# PCF8563.net
KiCad netlist of a schematic drawn in Altium Designer
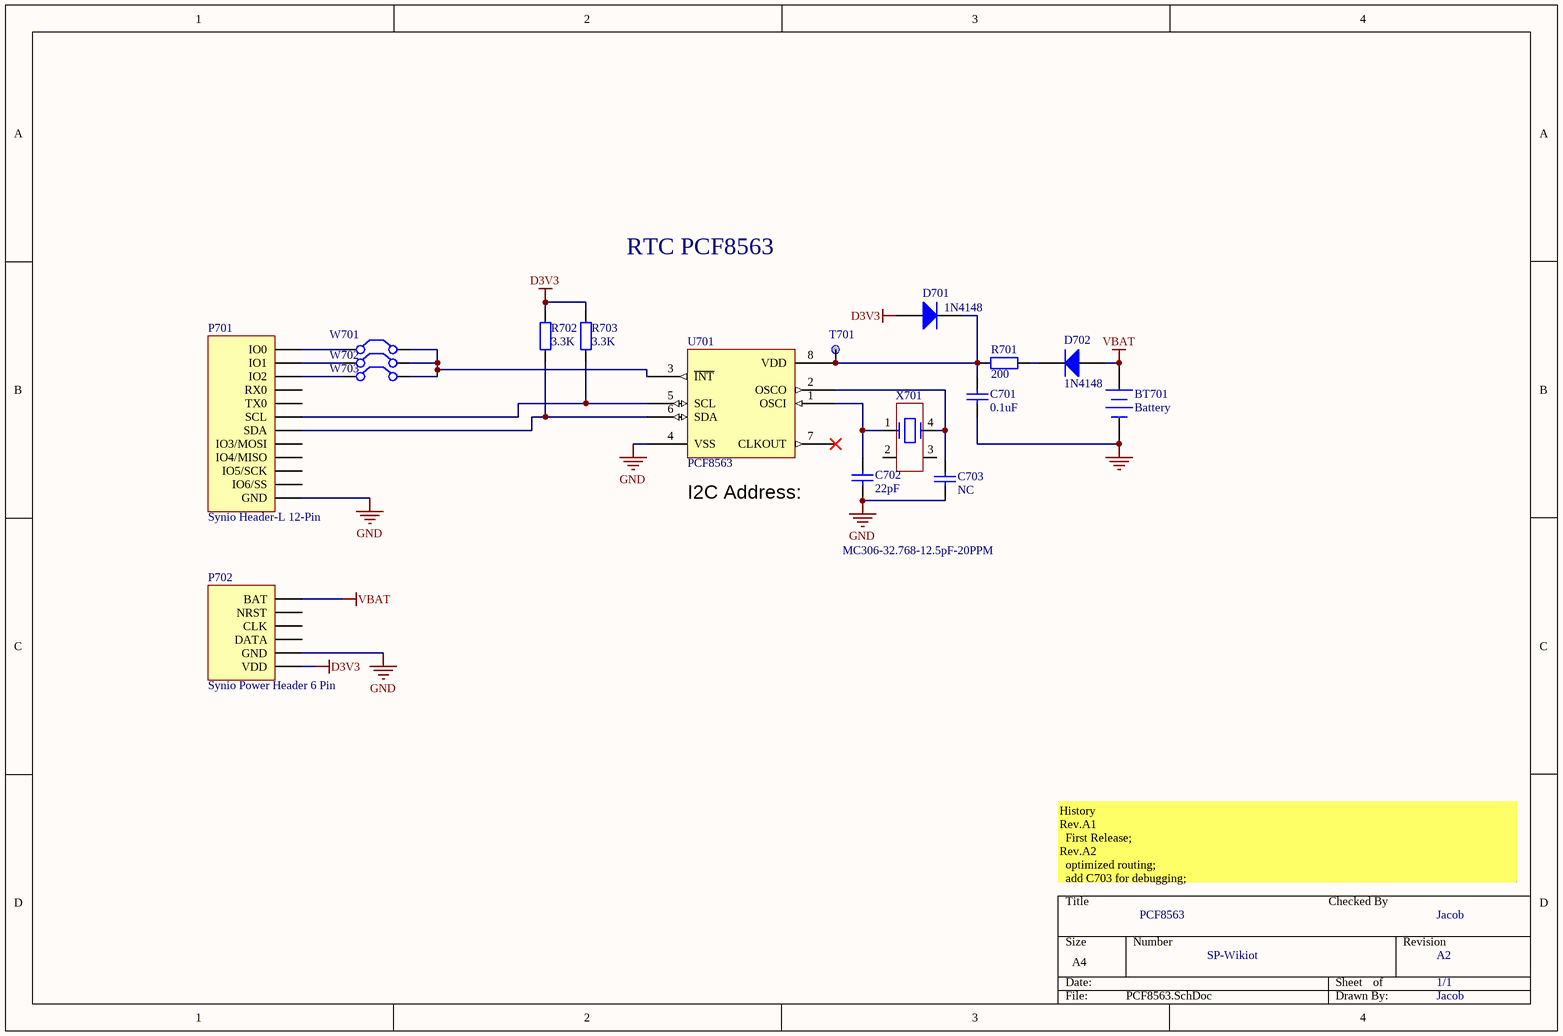
[diagram p0: PCF8563.SchDoc]

(export (version "E")
  (design (tool "Eeschema 10.0.6"))
  (components
    (comp (ref "BT701")
      (value "Battery")
      (footprint "BAT CR1220")
      (description "Multicell Battery")
      (fields (field (name "PUBLISHER") "Altium Limited"))
      (libsource (lib "Miscellaneous Devices") (part "Battery"))
    )
    (comp (ref "C701")
      (value "0.1uF")
      (footprint "0603M")
      (description "Capacitor")
      (libsource (lib "Studio") (part "Cap"))
    )
    (comp (ref "C702")
      (value "22pF")
      (footprint "0603M")
      (description "Capacitor")
      (libsource (lib "Studio") (part "Cap"))
    )
    (comp (ref "C703")
      (value "NC")
      (footprint "0603M")
      (description "Capacitor")
      (libsource (lib "Studio") (part "Cap"))
    )
    (comp (ref "D701")
      (value "1N4148")
      (footprint "1206")
      (description "1 Amp General Purpose Rectifier")
      (fields (field (name "PUBLISHER") "Altium Limited"))
      (libsource (lib "Misc") (part "Diode 1N4007"))
    )
    (comp (ref "D702")
      (value "1N4148")
      (footprint "1206")
      (description "1 Amp General Purpose Rectifier")
      (fields (field (name "PUBLISHER") "Altium Limited"))
      (libsource (lib "Misc") (part "Diode 1N4007"))
    )
    (comp (ref "P701")
      (value "Synio Header-L 12-Pin")
      (footprint "HDR1X12")
      (description "Synio Header-L, 12-Pin")
      (fields (field (name "PUBLISHER") "Altium Limited"))
      (libsource (lib "Connector") (part "Synio Header-L 12-Pin"))
    )
    (comp (ref "P702")
      (value "Synio Power Header 6 Pin")
      (footprint "HDR1X6/2.54MM")
      (libsource (lib "Connector") (part "Synio Power Header 6 Pin"))
    )
    (comp (ref "R701")
      (value "200")
      (footprint "R0603")
      (description "Resistor")
      (fields (field (name "PUBLISHER") "Altium Limited"))
      (libsource (lib "") (part "Res2_1"))
    )
    (comp (ref "R702")
      (value "3.3K")
      (footprint "R0603")
      (description "Resistor")
      (fields (field (name "PUBLISHER") "Altium Limited"))
      (libsource (lib "Miscellaneous Devices") (part "Res2"))
    )
    (comp (ref "R703")
      (value "3.3K")
      (footprint "R0603")
      (description "Resistor")
      (fields (field (name "PUBLISHER") "Altium Limited"))
      (libsource (lib "Miscellaneous Devices") (part "Res2"))
    )
    (comp (ref "T701")
      (value "TP")
      (footprint "TP")
      (description "Test Point")
      (libsource (lib "Misc") (part "TP"))
    )
    (comp (ref "U701")
      (value "PCF8563")
      (footprint "SO8W_M")
      (description "Real Time Clock/Calendar")
      (libsource (lib "Logic") (part "PCF8563"))
    )
    (comp (ref "W701")
      (value "Jumper2-1")
      (footprint "HDR1X2/2.00MM")
      (description "Jumper Wire")
      (fields (field (name "PUBLISHER") "Altium Limited"))
      (libsource (lib "Misc") (part "Jumper2-1"))
    )
    (comp (ref "W702")
      (value "Jumper2-1")
      (footprint "HDR1X2/2.00MM")
      (description "Jumper Wire")
      (fields (field (name "PUBLISHER") "Altium Limited"))
      (libsource (lib "Misc") (part "Jumper2-1"))
    )
    (comp (ref "W703")
      (value "Jumper2-1")
      (footprint "HDR1X2/2.00MM")
      (description "Jumper Wire")
      (fields (field (name "PUBLISHER") "Altium Limited"))
      (libsource (lib "Misc") (part "Jumper2-1"))
    )
    (comp (ref "X701")
      (value "MC306-32.768-12.5pF-20PPM")
      (footprint "SM8")
      (libsource (lib "Misc") (part "MC306"))
    )
  )
  (nets
    (net (code "1") (name "D3V3") (class "Default")
      (node (ref "D701") (pin "1") (pinfunction "A_1") (pintype "passive"))
      (node (ref "P702") (pin "1") (pinfunction "VDD_1") (pintype "passive"))
      (node (ref "R702") (pin "2") (pinfunction "2_2") (pintype "passive"))
      (node (ref "R703") (pin "2") (pinfunction "2_2") (pintype "passive"))
    )
    (net (code "2") (name "GND") (class "Default")
      (node (ref "BT701") (pin "2") (pinfunction "-_2") (pintype "passive"))
      (node (ref "C701") (pin "1") (pinfunction "1_1") (pintype "passive"))
      (node (ref "C702") (pin "1") (pinfunction "1_1") (pintype "passive"))
      (node (ref "C703") (pin "1") (pinfunction "1_1") (pintype "passive"))
      (node (ref "P701") (pin "1") (pinfunction "GND_1") (pintype "passive"))
      (node (ref "P702") (pin "2") (pinfunction "GND_2") (pintype "passive"))
      (node (ref "U701") (pin "4") (pinfunction "VSS_4") (pintype "power_in"))
    )
    (net (code "3") (name "Net-(D701-K)") (class "Default")
      (node (ref "C701") (pin "2") (pinfunction "2_2") (pintype "passive"))
      (node (ref "D701") (pin "2") (pinfunction "K_2") (pintype "passive"))
      (node (ref "R701") (pin "1") (pinfunction "1_1") (pintype "passive"))
      (node (ref "T701") (pin "1") (pinfunction "1_1") (pintype "passive"))
      (node (ref "U701") (pin "8") (pinfunction "VDD_8") (pintype "power_in"))
    )
    (net (code "4") (name "Net-(D702-K)") (class "Default")
      (node (ref "D702") (pin "2") (pinfunction "K_2") (pintype "passive"))
      (node (ref "R701") (pin "2") (pinfunction "2_2") (pintype "passive"))
    )
    (net (code "5") (name "Net-(P701-IO0)") (class "Default")
      (node (ref "P701") (pin "12") (pinfunction "IO0_12") (pintype "passive"))
      (node (ref "W701") (pin "1") (pinfunction "C1_1") (pintype "passive"))
    )
    (net (code "6") (name "Net-(P701-IO1)") (class "Default")
      (node (ref "P701") (pin "11") (pinfunction "IO1_11") (pintype "passive"))
      (node (ref "W702") (pin "1") (pinfunction "C1_1") (pintype "passive"))
    )
    (net (code "7") (name "Net-(P701-IO2)") (class "Default")
      (node (ref "P701") (pin "10") (pinfunction "IO2_10") (pintype "passive"))
      (node (ref "W703") (pin "1") (pinfunction "C1_1") (pintype "passive"))
    )
    (net (code "8") (name "Net-(P701-SCL)") (class "Default")
      (node (ref "P701") (pin "7") (pinfunction "SCL_7") (pintype "passive"))
      (node (ref "R703") (pin "1") (pinfunction "1_1") (pintype "passive"))
      (node (ref "U701") (pin "5") (pinfunction "SCL_5") (pintype "bidirectional"))
    )
    (net (code "9") (name "Net-(P701-SDA)") (class "Default")
      (node (ref "P701") (pin "6") (pinfunction "SDA_6") (pintype "passive"))
      (node (ref "R702") (pin "1") (pinfunction "1_1") (pintype "passive"))
      (node (ref "U701") (pin "6") (pinfunction "SDA_6") (pintype "bidirectional"))
    )
    (net (code "10") (name "Net-(U701-OSCI)") (class "Default")
      (node (ref "C702") (pin "2") (pinfunction "2_2") (pintype "passive"))
      (node (ref "U701") (pin "1") (pinfunction "OSCI_1") (pintype "input"))
      (node (ref "X701") (pin "1") (pinfunction "1_1") (pintype "passive"))
    )
    (net (code "11") (name "Net-(U701-OSCO)") (class "Default")
      (node (ref "C703") (pin "2") (pinfunction "2_2") (pintype "passive"))
      (node (ref "U701") (pin "2") (pinfunction "OSCO_2") (pintype "output"))
      (node (ref "X701") (pin "4") (pinfunction "4_4") (pintype "passive"))
    )
    (net (code "12") (name "Net-(U701-~{INT})") (class "Default")
      (node (ref "U701") (pin "3") (pinfunction "~{INT}_3") (pintype "output"))
      (node (ref "W701") (pin "2") (pinfunction "C2_2") (pintype "passive"))
      (node (ref "W702") (pin "2") (pinfunction "C2_2") (pintype "passive"))
      (node (ref "W703") (pin "2") (pinfunction "C2_2") (pintype "passive"))
    )
    (net (code "13") (name "VBAT") (class "Default")
      (node (ref "BT701") (pin "1") (pinfunction "+_1") (pintype "passive"))
      (node (ref "D702") (pin "1") (pinfunction "A_1") (pintype "passive"))
      (node (ref "P702") (pin "6") (pinfunction "BAT_6") (pintype "passive"))
    )
    (net (code "14") (name "unconnected-(P701-IO3{slash}MOSI-Pad5)") (class "Default")
      (node (ref "P701") (pin "5") (pinfunction "IO3/MOSI_5") (pintype "passive"))
    )
    (net (code "15") (name "unconnected-(P701-IO4{slash}MISO-Pad4)") (class "Default")
      (node (ref "P701") (pin "4") (pinfunction "IO4/MISO_4") (pintype "passive"))
    )
    (net (code "16") (name "unconnected-(P701-IO5{slash}SCK-Pad3)") (class "Default")
      (node (ref "P701") (pin "3") (pinfunction "IO5/SCK_3") (pintype "passive"))
    )
    (net (code "17") (name "unconnected-(P701-IO6{slash}SS-Pad2)") (class "Default")
      (node (ref "P701") (pin "2") (pinfunction "IO6/SS_2") (pintype "passive"))
    )
    (net (code "18") (name "unconnected-(P701-RX0-Pad9)") (class "Default")
      (node (ref "P701") (pin "9") (pinfunction "RX0_9") (pintype "passive"))
    )
    (net (code "19") (name "unconnected-(P701-TX0-Pad8)") (class "Default")
      (node (ref "P701") (pin "8") (pinfunction "TX0_8") (pintype "passive"))
    )
    (net (code "20") (name "unconnected-(P702-CLK-Pad4)") (class "Default")
      (node (ref "P702") (pin "4") (pinfunction "CLK_4") (pintype "passive"))
    )
    (net (code "21") (name "unconnected-(P702-DATA-Pad3)") (class "Default")
      (node (ref "P702") (pin "3") (pinfunction "DATA_3") (pintype "passive"))
    )
    (net (code "22") (name "unconnected-(P702-NRST-Pad5)") (class "Default")
      (node (ref "P702") (pin "5") (pinfunction "NRST_5") (pintype "passive"))
    )
    (net (code "23") (name "unconnected-(U701-CLKOUT-Pad7)") (class "Default")
      (node (ref "U701") (pin "7") (pinfunction "CLKOUT_7") (pintype "output+no_connect"))
    )
    (net (code "24") (name "unconnected-(X701-Pad2)") (class "Default")
      (node (ref "X701") (pin "2") (pinfunction "2_2") (pintype "passive"))
    )
    (net (code "25") (name "unconnected-(X701-Pad3)") (class "Default")
      (node (ref "X701") (pin "3") (pinfunction "3_3") (pintype "passive"))
    )
  )
)
